# ethernet_adapter.net
KiCad netlist of a schematic drawn in EAGLE
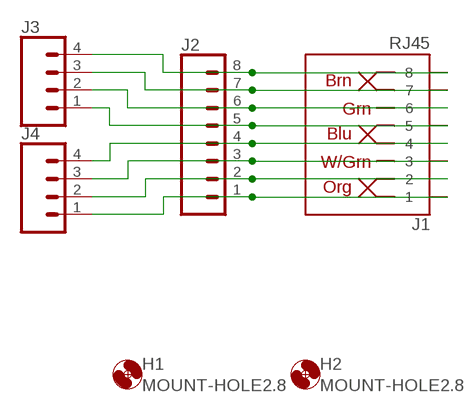
[diagram p0: schematic, sheet 1]

(export (version "E")
  (design (tool "Eeschema 10.0.6"))
  (components
    (comp (ref "H1")
      (value "MOUNT-HOLE2.8")
      (footprint "eagle-import:2,8")
      (libsource (lib "eagle-import") (part "MOUNT-HOLE2.8"))
    )
    (comp (ref "H2")
      (value "MOUNT-HOLE2.8")
      (footprint "eagle-import:2,8")
      (libsource (lib "eagle-import") (part "MOUNT-HOLE2.8"))
    )
    (comp (ref "J1")
      (value "RJ45")
      (footprint "eagle-import:RJ45-8")
      (libsource (lib "eagle-import") (part "RJ45-8"))
    )
    (comp (ref "J2")
      (value "CONN_08LONGPADS")
      (footprint "eagle-import:1X08_LONGPADS")
      (libsource (lib "eagle-import") (part "CONN_08LONGPADS"))
    )
    (comp (ref "J3")
      (value "CONN_04SCREW")
      (footprint "eagle-import:SCREWTERMINAL-3.5MM-4")
      (libsource (lib "eagle-import") (part "CONN_04SCREW"))
    )
    (comp (ref "J4")
      (value "CONN_04SCREW")
      (footprint "eagle-import:SCREWTERMINAL-3.5MM-4")
      (libsource (lib "eagle-import") (part "CONN_04SCREW"))
    )
  )
  (nets
    (net (code "1") (name "Net-(J1-Pad1)") (class "Default")
      (node (ref "J1") (pin "1") (pinfunction "1_1") (pintype "bidirectional"))
      (node (ref "J2") (pin "1") (pinfunction "1_1") (pintype "passive"))
      (node (ref "J4") (pin "1") (pinfunction "1_1") (pintype "passive"))
    )
    (net (code "2") (name "Net-(J1-Pad2)") (class "Default")
      (node (ref "J1") (pin "2") (pinfunction "2_2") (pintype "bidirectional"))
      (node (ref "J2") (pin "2") (pinfunction "2_2") (pintype "passive"))
      (node (ref "J4") (pin "2") (pinfunction "2_2") (pintype "passive"))
    )
    (net (code "3") (name "Net-(J1-Pad3)") (class "Default")
      (node (ref "J1") (pin "3") (pinfunction "3_3") (pintype "bidirectional"))
      (node (ref "J2") (pin "3") (pinfunction "3_3") (pintype "passive"))
      (node (ref "J4") (pin "3") (pinfunction "3_3") (pintype "passive"))
    )
    (net (code "4") (name "Net-(J1-Pad4)") (class "Default")
      (node (ref "J1") (pin "4") (pinfunction "4_4") (pintype "bidirectional"))
      (node (ref "J2") (pin "4") (pinfunction "4_4") (pintype "passive"))
      (node (ref "J4") (pin "4") (pinfunction "4_4") (pintype "passive"))
    )
    (net (code "5") (name "Net-(J1-Pad5)") (class "Default")
      (node (ref "J1") (pin "5") (pinfunction "5_5") (pintype "bidirectional"))
      (node (ref "J2") (pin "5") (pinfunction "5_5") (pintype "passive"))
      (node (ref "J3") (pin "1") (pinfunction "1_1") (pintype "passive"))
    )
    (net (code "6") (name "Net-(J1-Pad6)") (class "Default")
      (node (ref "J1") (pin "6") (pinfunction "6_6") (pintype "bidirectional"))
      (node (ref "J2") (pin "6") (pinfunction "6_6") (pintype "passive"))
      (node (ref "J3") (pin "2") (pinfunction "2_2") (pintype "passive"))
    )
    (net (code "7") (name "Net-(J1-Pad7)") (class "Default")
      (node (ref "J1") (pin "7") (pinfunction "7_7") (pintype "bidirectional"))
      (node (ref "J2") (pin "7") (pinfunction "7_7") (pintype "passive"))
      (node (ref "J3") (pin "3") (pinfunction "3_3") (pintype "passive"))
    )
    (net (code "8") (name "Net-(J1-Pad8)") (class "Default")
      (node (ref "J1") (pin "8") (pinfunction "8_8") (pintype "bidirectional"))
      (node (ref "J2") (pin "8") (pinfunction "8_8") (pintype "passive"))
      (node (ref "J3") (pin "4") (pinfunction "4_4") (pintype "passive"))
    )
  )
)
